# coil-control-module-v3.net
KiCad netlist of a schematic drawn in EAGLE
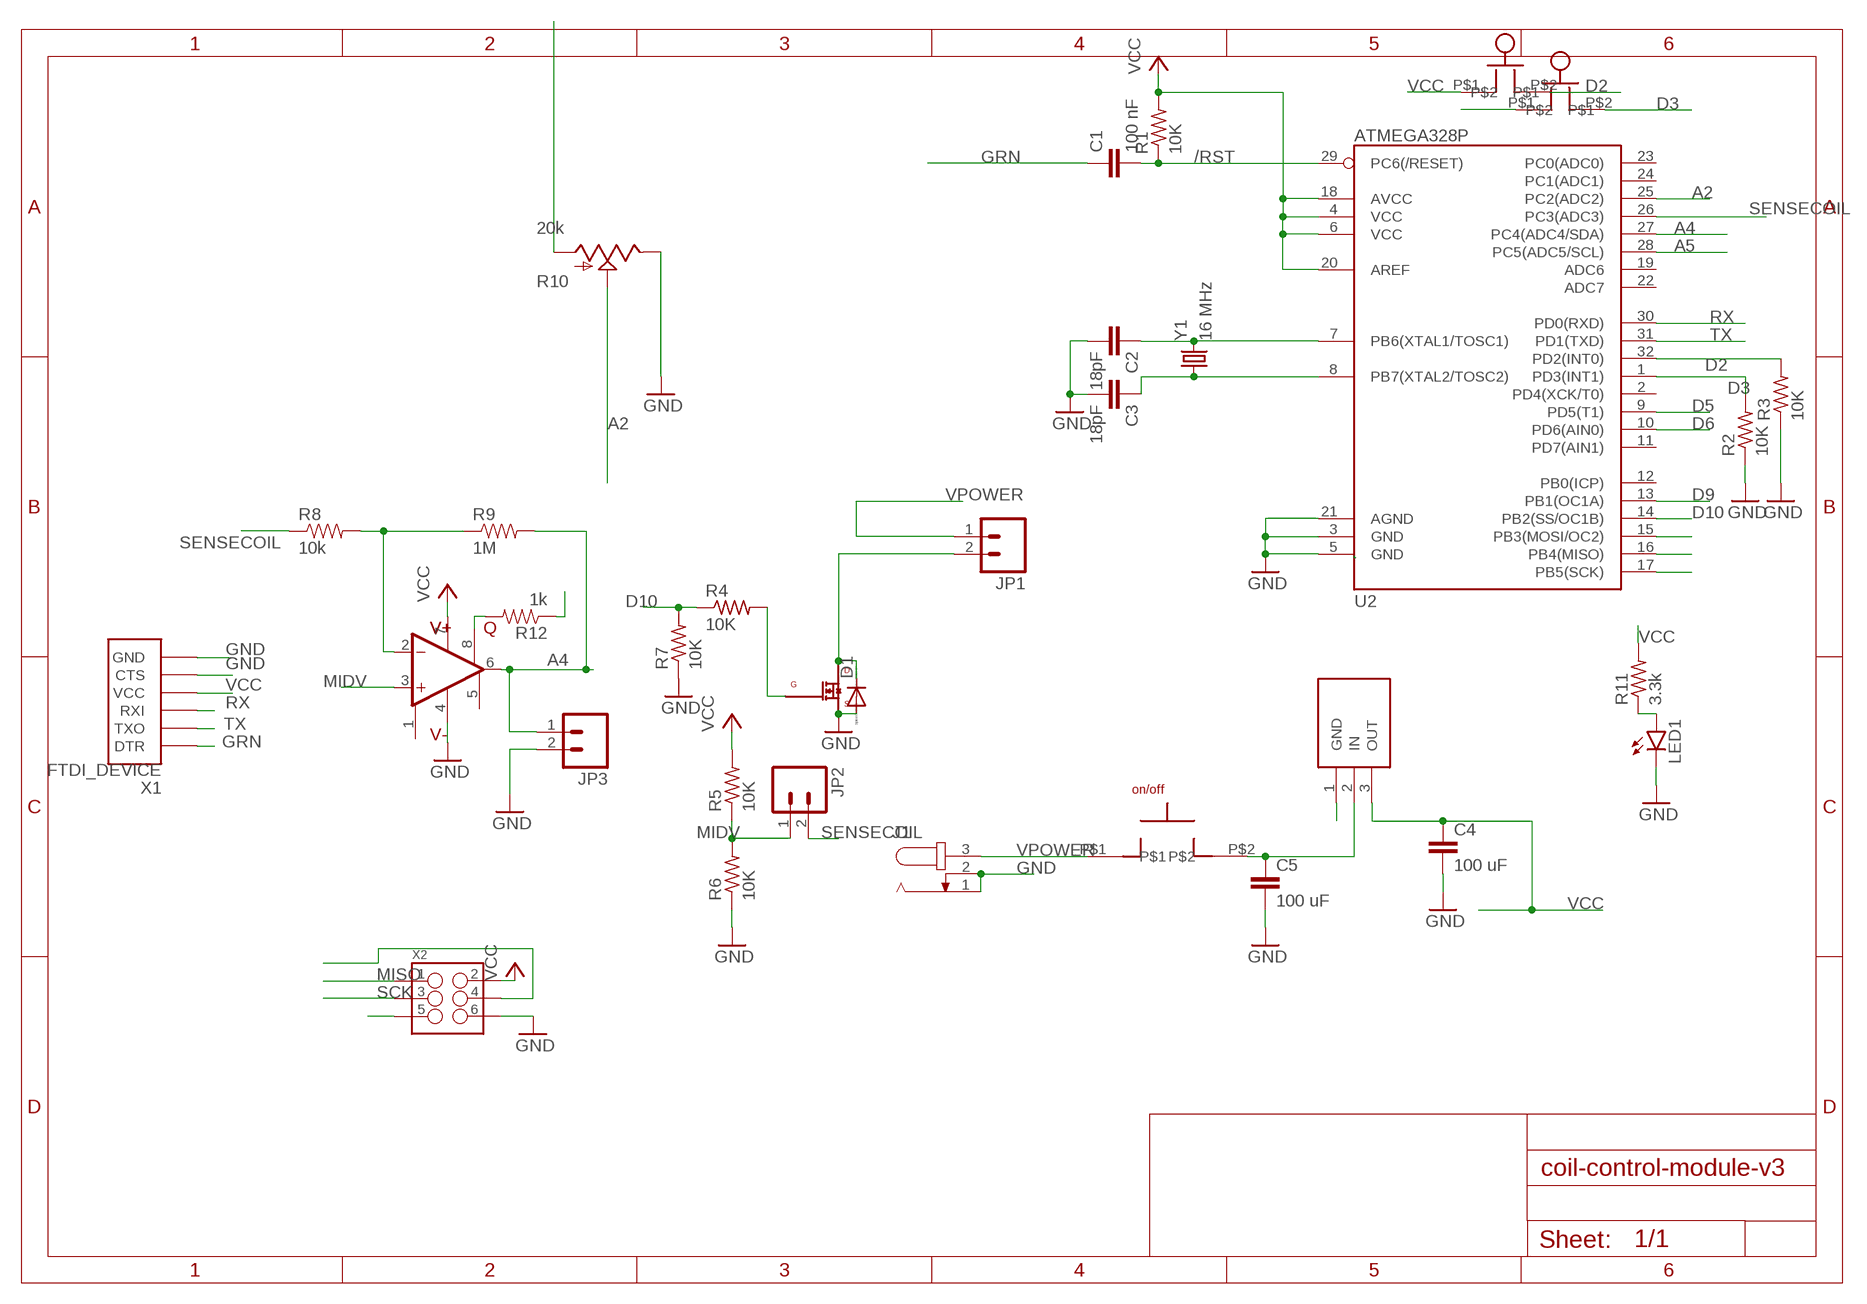
[diagram p0: schematic, sheet 1]

(export (version "E")
  (design (tool "Eeschema 10.0.6"))
  (components
    (comp (ref "C1")
      (value "100 nF")
      (footprint "eagle-import:0603-CAP")
      (libsource (lib "eagle-import") (part "SparkFun-Passives_CAP0603-CAP"))
    )
    (comp (ref "C2")
      (value "18pF")
      (footprint "eagle-import:C0603")
      (libsource (lib "eagle-import") (part "C-EUC0603"))
    )
    (comp (ref "C3")
      (value "18pF")
      (footprint "eagle-import:C0603")
      (libsource (lib "eagle-import") (part "C-EUC0603"))
    )
    (comp (ref "C4")
      (value "100 uF")
      (footprint "eagle-import:1206")
      (libsource (lib "eagle-import") (part "CAP1206"))
    )
    (comp (ref "C5")
      (value "100 uF")
      (footprint "eagle-import:1206")
      (libsource (lib "eagle-import") (part "CAP1206"))
    )
    (comp (ref "D1")
      (value "DIODE-DO-214AC")
      (footprint "eagle-import:DO-214AC")
      (libsource (lib "eagle-import") (part "DIODE-DO-214AC"))
    )
    (comp (ref "J1")
      (value "JACK-PLUG1")
      (footprint "eagle-import:SPC4078")
      (libsource (lib "eagle-import") (part "JACK-PLUG1"))
    )
    (comp (ref "JP1")
      (value "M02PTH")
      (footprint "eagle-import:1X02")
      (libsource (lib "eagle-import") (part "M02PTH"))
    )
    (comp (ref "JP2")
      (value "M02PTH")
      (footprint "eagle-import:1X02")
      (libsource (lib "eagle-import") (part "M02PTH"))
    )
    (comp (ref "JP3")
      (value "M02PTH")
      (footprint "eagle-import:1X02")
      (libsource (lib "eagle-import") (part "M02PTH"))
    )
    (comp (ref "LED1")
      (value "LED-3MM-NO_SILK")
      (footprint "eagle-import:LED3MM-NS")
      (libsource (lib "eagle-import") (part "LED-3MM-NO_SILK"))
    )
    (comp (ref "R1")
      (value "10K")
      (footprint "eagle-import:R0603")
      (libsource (lib "eagle-import") (part "R-US_R0603"))
    )
    (comp (ref "R2")
      (value "10K")
      (footprint "eagle-import:R0603")
      (libsource (lib "eagle-import") (part "R-US_R0603"))
    )
    (comp (ref "R3")
      (value "10K")
      (footprint "eagle-import:R0603")
      (libsource (lib "eagle-import") (part "R-US_R0603"))
    )
    (comp (ref "R4")
      (value "10K")
      (footprint "eagle-import:R0603")
      (libsource (lib "eagle-import") (part "R-US_R0603"))
    )
    (comp (ref "R5")
      (value "10K")
      (footprint "eagle-import:R0603")
      (libsource (lib "eagle-import") (part "R-US_R0603"))
    )
    (comp (ref "R6")
      (value "10K")
      (footprint "eagle-import:R0603")
      (libsource (lib "eagle-import") (part "R-US_R0603"))
    )
    (comp (ref "R7")
      (value "10K")
      (footprint "eagle-import:R0603")
      (libsource (lib "eagle-import") (part "R-US_R0603"))
    )
    (comp (ref "R8")
      (value "10k")
      (footprint "eagle-import:0603-RES")
      (libsource (lib "eagle-import") (part "RESISTOR0603"))
    )
    (comp (ref "R9")
      (value "1M")
      (footprint "eagle-import:0805")
      (libsource (lib "eagle-import") (part "RESISTOR0805-RES"))
    )
    (comp (ref "R10")
      (value "20k")
      (footprint "eagle-import:ALPS_POT_KIT")
      (libsource (lib "eagle-import") (part "POTALPS-KIT"))
    )
    (comp (ref "R11")
      (value "3.3k")
      (footprint "eagle-import:R0603")
      (libsource (lib "eagle-import") (part "R-US_R0603"))
    )
    (comp (ref "R12")
      (value "1k")
      (footprint "eagle-import:0603-RES")
      (libsource (lib "eagle-import") (part "RESISTOR0603"))
    )
    (comp (ref "SW1")
      (value "CW182-ND")
      (footprint "eagle-import:CW182-ND")
      (libsource (lib "eagle-import") (part "CW182-ND"))
    )
    (comp (ref "SW2")
      (value "BUTTON")
      (footprint "eagle-import:BUTTON")
      (libsource (lib "eagle-import") (part "BUTTON"))
    )
    (comp (ref "SW3")
      (value "BUTTON")
      (footprint "eagle-import:BUTTON")
      (libsource (lib "eagle-import") (part "BUTTON"))
    )
    (comp (ref "U$5")
      (value "LM4250")
      (footprint "eagle-import:DIP08")
      (libsource (lib "eagle-import") (part "LM4250"))
    )
    (comp (ref "U$6")
      (value "IRLML0060")
      (footprint "eagle-import:SOT-23")
      (libsource (lib "eagle-import") (part "IRLML0060"))
    )
    (comp (ref "U2")
      (value "ATMEGA328P")
      (footprint "eagle-import:TQFP32-08")
      (libsource (lib "eagle-import") (part "ATMEGA328_SMT"))
    )
    (comp (ref "U4")
      (value "MCP1700")
      (footprint "eagle-import:TO92-3")
      (libsource (lib "eagle-import") (part "MCP1700"))
    )
    (comp (ref "X1")
      (value "FTDI_DEVICE")
      (footprint "eagle-import:FTDI_DEVICE_SIDE")
      (libsource (lib "eagle-import") (part "FTDI_DEVICE"))
    )
    (comp (ref "X2")
      (value "M03X2NO_SILK")
      (footprint "eagle-import:2X3-NS")
      (libsource (lib "eagle-import") (part "M03X2NO_SILK"))
    )
    (comp (ref "Y1")
      (value "16 MHz")
      (footprint "eagle-import:CRYSTAL-SMD-5X3")
      (libsource (lib "eagle-import") (part "CRYSTAL5X3"))
    )
  )
  (nets
    (net (code "1") (name "/A2") (class "Default")
      (node (ref "R10") (pin "P$2") (pinfunction "S_P$2") (pintype "passive"))
      (node (ref "U2") (pin "25") (pinfunction "PC2(ADC2)_25") (pintype "bidirectional"))
    )
    (net (code "2") (name "/A4") (class "Default")
      (node (ref "JP3") (pin "1") (pinfunction "1_1") (pintype "passive"))
      (node (ref "R9") (pin "2") (pinfunction "2_2") (pintype "passive"))
      (node (ref "U$5") (pin "6") (pinfunction "OUT_6") (pintype "output"))
      (node (ref "U2") (pin "27") (pinfunction "PC4(ADC4/SDA)_27") (pintype "bidirectional"))
    )
    (net (code "3") (name "/A5") (class "Default")
      (node (ref "U2") (pin "28") (pinfunction "PC5(ADC5/SCL)_28") (pintype "bidirectional"))
    )
    (net (code "4") (name "/D2") (class "Default")
      (node (ref "R3") (pin "2") (pinfunction "2_2") (pintype "passive"))
      (node (ref "SW2") (pin "P$2") (pinfunction "P$2_P$2") (pintype "bidirectional"))
      (node (ref "U2") (pin "32") (pinfunction "PD2(INT0)_32") (pintype "bidirectional"))
    )
    (net (code "5") (name "/D3") (class "Default")
      (node (ref "R2") (pin "2") (pinfunction "2_2") (pintype "passive"))
      (node (ref "SW3") (pin "P$2") (pinfunction "P$2_P$2") (pintype "bidirectional"))
      (node (ref "U2") (pin "1") (pinfunction "PD3(INT1)_1") (pintype "bidirectional"))
    )
    (net (code "6") (name "/D5") (class "Default")
      (node (ref "U2") (pin "9") (pinfunction "PD5(T1)_9") (pintype "bidirectional"))
    )
    (net (code "7") (name "/D6") (class "Default")
      (node (ref "U2") (pin "10") (pinfunction "PD6(AIN0)_10") (pintype "bidirectional"))
    )
    (net (code "8") (name "/D9") (class "Default")
      (node (ref "U2") (pin "13") (pinfunction "PB1(OC1A)_13") (pintype "bidirectional"))
    )
    (net (code "9") (name "/D10") (class "Default")
      (node (ref "R4") (pin "1") (pinfunction "1_1") (pintype "passive"))
      (node (ref "R7") (pin "2") (pinfunction "2_2") (pintype "passive"))
      (node (ref "U2") (pin "14") (pinfunction "PB2(SS/OC1B)_14") (pintype "bidirectional"))
    )
    (net (code "10") (name "/GRN") (class "Default")
      (node (ref "C1") (pin "1") (pinfunction "1_1") (pintype "passive"))
      (node (ref "X1") (pin "P$1") (pinfunction "DTR_P$1") (pintype "bidirectional"))
    )
    (net (code "11") (name "/MIDV") (class "Default")
      (node (ref "JP2") (pin "1") (pinfunction "1_1") (pintype "passive"))
      (node (ref "R12") (pin "1") (pinfunction "1_1") (pintype "passive"))
      (node (ref "R5") (pin "1") (pinfunction "1_1") (pintype "passive"))
      (node (ref "R6") (pin "2") (pinfunction "2_2") (pintype "passive"))
      (node (ref "U$5") (pin "3") (pinfunction "+IN_3") (pintype "input"))
    )
    (net (code "12") (name "/MISO") (class "Default")
      (node (ref "U2") (pin "16") (pinfunction "PB4(MISO)_16") (pintype "bidirectional"))
      (node (ref "X2") (pin "1") (pinfunction "1_1") (pintype "bidirectional"))
    )
    (net (code "13") (name "/MOSI") (class "Default")
      (node (ref "U2") (pin "15") (pinfunction "PB3(MOSI/OC2)_15") (pintype "bidirectional"))
      (node (ref "X2") (pin "4") (pinfunction "4_4") (pintype "bidirectional"))
    )
    (net (code "14") (name "/RX") (class "Default")
      (node (ref "U2") (pin "30") (pinfunction "PD0(RXD)_30") (pintype "bidirectional"))
      (node (ref "X1") (pin "P$3") (pinfunction "RXI_P$3") (pintype "bidirectional"))
    )
    (net (code "15") (name "/SCK") (class "Default")
      (node (ref "U2") (pin "17") (pinfunction "PB5(SCK)_17") (pintype "bidirectional"))
      (node (ref "X2") (pin "3") (pinfunction "3_3") (pintype "bidirectional"))
    )
    (net (code "16") (name "/SENSECOIL") (class "Default")
      (node (ref "JP2") (pin "2") (pinfunction "2_2") (pintype "passive"))
      (node (ref "R8") (pin "1") (pinfunction "1_1") (pintype "passive"))
      (node (ref "U2") (pin "26") (pinfunction "PC3(ADC3)_26") (pintype "bidirectional"))
    )
    (net (code "17") (name "/TX") (class "Default")
      (node (ref "U2") (pin "31") (pinfunction "PD1(TXD)_31") (pintype "bidirectional"))
      (node (ref "X1") (pin "P$2") (pinfunction "TXO_P$2") (pintype "bidirectional"))
    )
    (net (code "18") (name "/VPOWER") (class "Default")
      (node (ref "J1") (pin "3") (pinfunction "3_3") (pintype "passive"))
      (node (ref "JP1") (pin "1") (pinfunction "1_1") (pintype "passive"))
      (node (ref "SW1") (pin "P$1") (pinfunction "P$1_P$1") (pintype "bidirectional"))
    )
    (net (code "19") (name "/{slash}RST") (class "Default")
      (node (ref "C1") (pin "2") (pinfunction "2_2") (pintype "passive"))
      (node (ref "R1") (pin "1") (pinfunction "1_1") (pintype "passive"))
      (node (ref "U2") (pin "29") (pinfunction "PC6(/RESET)_29") (pintype "bidirectional"))
      (node (ref "X2") (pin "5") (pinfunction "5_5") (pintype "bidirectional"))
    )
    (net (code "20") (name "GND") (class "Default")
      (node (ref "C2") (pin "2") (pinfunction "2_2") (pintype "passive"))
      (node (ref "C3") (pin "2") (pinfunction "2_2") (pintype "passive"))
      (node (ref "C4") (pin "2") (pinfunction "2_2") (pintype "passive"))
      (node (ref "C5") (pin "2") (pinfunction "2_2") (pintype "passive"))
      (node (ref "D1") (pin "A") (pinfunction "A_A") (pintype "passive"))
      (node (ref "J1") (pin "1") (pinfunction "1_1") (pintype "passive"))
      (node (ref "J1") (pin "2") (pinfunction "2_2") (pintype "passive"))
      (node (ref "JP3") (pin "2") (pinfunction "2_2") (pintype "passive"))
      (node (ref "LED1") (pin "K") (pinfunction "C_K") (pintype "passive"))
      (node (ref "R10") (pin "P$1") (pinfunction "E_P$1") (pintype "passive"))
      (node (ref "R2") (pin "1") (pinfunction "1_1") (pintype "passive"))
      (node (ref "R3") (pin "1") (pinfunction "1_1") (pintype "passive"))
      (node (ref "R6") (pin "1") (pinfunction "1_1") (pintype "passive"))
      (node (ref "R7") (pin "1") (pinfunction "1_1") (pintype "passive"))
      (node (ref "U$5") (pin "4") (pinfunction "V-_4") (pintype "power_in"))
      (node (ref "U$6") (pin "2") (pinfunction "SOURCE_2") (pintype "bidirectional"))
      (node (ref "U2") (pin "21") (pinfunction "AGND_21") (pintype "bidirectional"))
      (node (ref "U2") (pin "3") (pinfunction "GND_3") (pintype "bidirectional"))
      (node (ref "U2") (pin "5") (pinfunction "GND_5") (pintype "bidirectional"))
      (node (ref "U4") (pin "1") (pinfunction "GND_1") (pintype "bidirectional"))
      (node (ref "X1") (pin "P$5") (pinfunction "CTS_P$5") (pintype "bidirectional"))
      (node (ref "X1") (pin "P$6") (pinfunction "GND_P$6") (pintype "bidirectional"))
      (node (ref "X2") (pin "6") (pinfunction "6_6") (pintype "bidirectional"))
    )
    (net (code "21") (name "Net-(LED1-PadA)") (class "Default")
      (node (ref "LED1") (pin "A") (pinfunction "A_A") (pintype "passive"))
      (node (ref "R11") (pin "1") (pinfunction "1_1") (pintype "passive"))
    )
    (net (code "22") (name "Net-(U$5--IN)") (class "Default")
      (node (ref "R8") (pin "2") (pinfunction "2_2") (pintype "passive"))
      (node (ref "R9") (pin "1") (pinfunction "1_1") (pintype "passive"))
      (node (ref "U$5") (pin "2") (pinfunction "-IN_2") (pintype "input"))
    )
    (net (code "23") (name "Net-(U$5-QUIES)") (class "Default")
      (node (ref "R12") (pin "2") (pinfunction "2_2") (pintype "passive"))
      (node (ref "U$5") (pin "8") (pinfunction "QUIES_8") (pintype "bidirectional"))
    )
    (net (code "24") (name "Net-(U$6-DRAIN)") (class "Default")
      (node (ref "D1") (pin "C") (pinfunction "C_C") (pintype "passive"))
      (node (ref "JP1") (pin "2") (pinfunction "2_2") (pintype "passive"))
      (node (ref "U$6") (pin "3") (pinfunction "DRAIN_3") (pintype "bidirectional"))
    )
    (net (code "25") (name "Net-(U$6-GATE)") (class "Default")
      (node (ref "R4") (pin "2") (pinfunction "2_2") (pintype "passive"))
      (node (ref "U$6") (pin "1") (pinfunction "GATE_1") (pintype "bidirectional"))
    )
    (net (code "26") (name "Net-(U2-PB6(XTAL1{slash}TOSC1))") (class "Default")
      (node (ref "C2") (pin "1") (pinfunction "1_1") (pintype "passive"))
      (node (ref "U2") (pin "7") (pinfunction "PB6(XTAL1/TOSC1)_7") (pintype "bidirectional"))
      (node (ref "Y1") (pin "3") (pinfunction "2_3") (pintype "passive"))
    )
    (net (code "27") (name "Net-(U2-PB7(XTAL2{slash}TOSC2))") (class "Default")
      (node (ref "C3") (pin "1") (pinfunction "1_1") (pintype "passive"))
      (node (ref "U2") (pin "8") (pinfunction "PB7(XTAL2/TOSC2)_8") (pintype "bidirectional"))
      (node (ref "Y1") (pin "1") (pinfunction "1_1") (pintype "passive"))
    )
    (net (code "28") (name "Net-(U4-IN)") (class "Default")
      (node (ref "C5") (pin "1") (pinfunction "1_1") (pintype "passive"))
      (node (ref "SW1") (pin "P$2") (pinfunction "P$2_P$2") (pintype "bidirectional"))
      (node (ref "U4") (pin "2") (pinfunction "IN_2") (pintype "bidirectional"))
    )
    (net (code "29") (name "VCC") (class "Default")
      (node (ref "C4") (pin "1") (pinfunction "1_1") (pintype "passive"))
      (node (ref "R1") (pin "2") (pinfunction "2_2") (pintype "passive"))
      (node (ref "R10") (pin "P$3") (pinfunction "A_P$3") (pintype "passive"))
      (node (ref "R11") (pin "2") (pinfunction "2_2") (pintype "passive"))
      (node (ref "R5") (pin "2") (pinfunction "2_2") (pintype "passive"))
      (node (ref "SW2") (pin "P$1") (pinfunction "P$1_P$1") (pintype "bidirectional"))
      (node (ref "SW3") (pin "P$1") (pinfunction "P$1_P$1") (pintype "bidirectional"))
      (node (ref "U$5") (pin "7") (pinfunction "V+_7") (pintype "power_in"))
      (node (ref "U2") (pin "18") (pinfunction "AVCC_18") (pintype "bidirectional"))
      (node (ref "U2") (pin "20") (pinfunction "AREF_20") (pintype "bidirectional"))
      (node (ref "U2") (pin "4") (pinfunction "VCC_4") (pintype "bidirectional"))
      (node (ref "U2") (pin "6") (pinfunction "VCC_6") (pintype "bidirectional"))
      (node (ref "U4") (pin "3") (pinfunction "OUT_3") (pintype "bidirectional"))
      (node (ref "X1") (pin "P$4") (pinfunction "VCC_P$4") (pintype "bidirectional"))
      (node (ref "X2") (pin "2") (pinfunction "2_2") (pintype "bidirectional"))
    )
    (net (code "30") (name "unconnected-(U$5-NULL1-Pad1)") (class "Default")
      (node (ref "U$5") (pin "1") (pinfunction "NULL1_1") (pintype "bidirectional"))
    )
    (net (code "31") (name "unconnected-(U$5-NULL2-Pad5)") (class "Default")
      (node (ref "U$5") (pin "5") (pinfunction "NULL2_5") (pintype "bidirectional"))
    )
    (net (code "32") (name "unconnected-(U2-ADC6-Pad19)") (class "Default")
      (node (ref "U2") (pin "19") (pinfunction "ADC6_19") (pintype "bidirectional"))
    )
    (net (code "33") (name "unconnected-(U2-ADC7-Pad22)") (class "Default")
      (node (ref "U2") (pin "22") (pinfunction "ADC7_22") (pintype "bidirectional"))
    )
    (net (code "34") (name "unconnected-(U2-PB0(ICP)-Pad12)") (class "Default")
      (node (ref "U2") (pin "12") (pinfunction "PB0(ICP)_12") (pintype "bidirectional"))
    )
    (net (code "35") (name "unconnected-(U2-PC0(ADC0)-Pad23)") (class "Default")
      (node (ref "U2") (pin "23") (pinfunction "PC0(ADC0)_23") (pintype "bidirectional"))
    )
    (net (code "36") (name "unconnected-(U2-PC1(ADC1)-Pad24)") (class "Default")
      (node (ref "U2") (pin "24") (pinfunction "PC1(ADC1)_24") (pintype "bidirectional"))
    )
    (net (code "37") (name "unconnected-(U2-PD4(XCK{slash}T0)-Pad2)") (class "Default")
      (node (ref "U2") (pin "2") (pinfunction "PD4(XCK/T0)_2") (pintype "bidirectional"))
    )
    (net (code "38") (name "unconnected-(U2-PD7(AIN1)-Pad11)") (class "Default")
      (node (ref "U2") (pin "11") (pinfunction "PD7(AIN1)_11") (pintype "bidirectional"))
    )
  )
)
